# module_slot_CON.net
KiCad netlist of a schematic drawn in Altium Designer
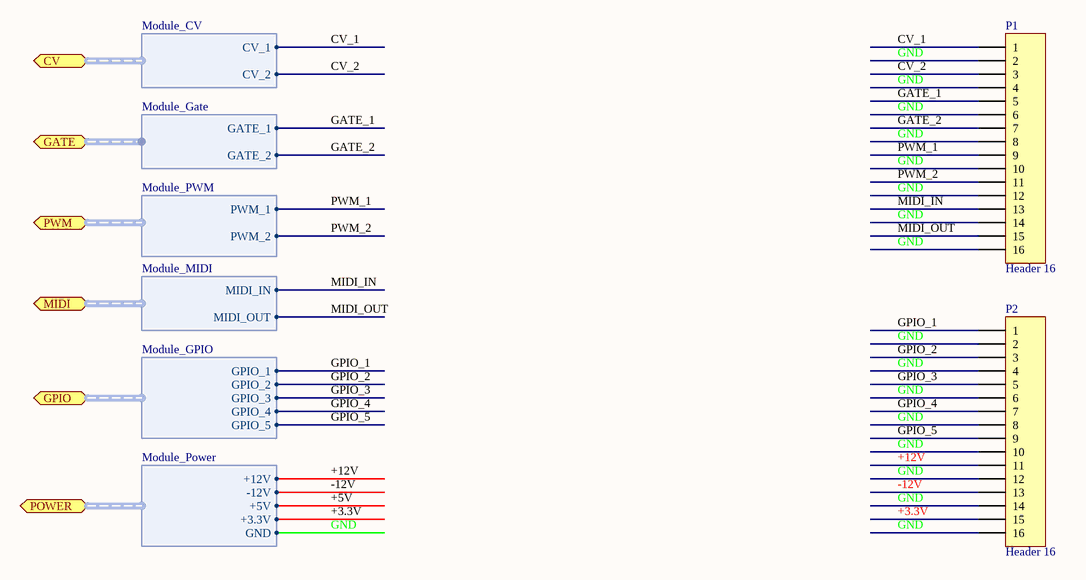
[diagram p0: module_slot_CON.SchDoc]

(export (version "E")
  (design (tool "Eeschema 10.0.6"))
  (components
    (comp (ref "P1")
      (value "Header 16")
      (footprint "HDR1X16")
      (description "Header, 16-Pin")
      (fields (field (name "PUBLISHER") "Altium Limited"))
      (libsource (lib "Miscellaneous Connectors") (part "Header 16"))
    )
    (comp (ref "P2")
      (value "Header 16")
      (footprint "HDR1X16")
      (description "Header, 16-Pin")
      (fields (field (name "PUBLISHER") "Altium Limited"))
      (libsource (lib "Miscellaneous Connectors") (part "Header 16"))
    )
  )
  (nets
    (net (code "7") (name "/+3.3V") (class "Default")
      (node (ref "P2") (pin "15") (pinfunction "15_15") (pintype "passive"))
    )
    (net (code "9") (name "/+12V") (class "Default")
      (node (ref "P2") (pin "11") (pinfunction "11_11") (pintype "passive"))
    )
    (net (code "10") (name "/-12V") (class "Default")
      (node (ref "P2") (pin "13") (pinfunction "13_13") (pintype "passive"))
    )
    (net (code "11") (name "/CV_1") (class "Default")
      (node (ref "P1") (pin "1") (pinfunction "1_1") (pintype "passive"))
    )
    (net (code "12") (name "/CV_2") (class "Default")
      (node (ref "P1") (pin "3") (pinfunction "3_3") (pintype "passive"))
    )
    (net (code "13") (name "/GATE_1") (class "Default")
      (node (ref "P1") (pin "5") (pinfunction "5_5") (pintype "passive"))
    )
    (net (code "14") (name "/GATE_2") (class "Default")
      (node (ref "P1") (pin "7") (pinfunction "7_7") (pintype "passive"))
    )
    (net (code "15") (name "/GND") (class "Default")
      (node (ref "P1") (pin "10") (pinfunction "10_10") (pintype "passive"))
      (node (ref "P1") (pin "12") (pinfunction "12_12") (pintype "passive"))
      (node (ref "P1") (pin "14") (pinfunction "14_14") (pintype "passive"))
      (node (ref "P1") (pin "16") (pinfunction "16_16") (pintype "passive"))
      (node (ref "P1") (pin "2") (pinfunction "2_2") (pintype "passive"))
      (node (ref "P1") (pin "4") (pinfunction "4_4") (pintype "passive"))
      (node (ref "P1") (pin "6") (pinfunction "6_6") (pintype "passive"))
      (node (ref "P1") (pin "8") (pinfunction "8_8") (pintype "passive"))
      (node (ref "P2") (pin "10") (pinfunction "10_10") (pintype "passive"))
      (node (ref "P2") (pin "12") (pinfunction "12_12") (pintype "passive"))
      (node (ref "P2") (pin "14") (pinfunction "14_14") (pintype "passive"))
      (node (ref "P2") (pin "16") (pinfunction "16_16") (pintype "passive"))
      (node (ref "P2") (pin "2") (pinfunction "2_2") (pintype "passive"))
      (node (ref "P2") (pin "4") (pinfunction "4_4") (pintype "passive"))
      (node (ref "P2") (pin "6") (pinfunction "6_6") (pintype "passive"))
      (node (ref "P2") (pin "8") (pinfunction "8_8") (pintype "passive"))
    )
    (net (code "16") (name "/GPIO_1") (class "Default")
      (node (ref "P2") (pin "1") (pinfunction "1_1") (pintype "passive"))
    )
    (net (code "17") (name "/GPIO_2") (class "Default")
      (node (ref "P2") (pin "3") (pinfunction "3_3") (pintype "passive"))
    )
    (net (code "18") (name "/GPIO_3") (class "Default")
      (node (ref "P2") (pin "5") (pinfunction "5_5") (pintype "passive"))
    )
    (net (code "19") (name "/GPIO_4") (class "Default")
      (node (ref "P2") (pin "7") (pinfunction "7_7") (pintype "passive"))
    )
    (net (code "20") (name "/GPIO_5") (class "Default")
      (node (ref "P2") (pin "9") (pinfunction "9_9") (pintype "passive"))
    )
    (net (code "21") (name "/MIDI_IN") (class "Default")
      (node (ref "P1") (pin "13") (pinfunction "13_13") (pintype "passive"))
    )
    (net (code "22") (name "/MIDI_OUT") (class "Default")
      (node (ref "P1") (pin "15") (pinfunction "15_15") (pintype "passive"))
    )
    (net (code "23") (name "/PWM_1") (class "Default")
      (node (ref "P1") (pin "9") (pinfunction "9_9") (pintype "passive"))
    )
    (net (code "24") (name "/PWM_2") (class "Default")
      (node (ref "P1") (pin "11") (pinfunction "11_11") (pintype "passive"))
    )
  )
)
